# DDRmem.net
KiCad netlist of a schematic drawn in Altium Designer
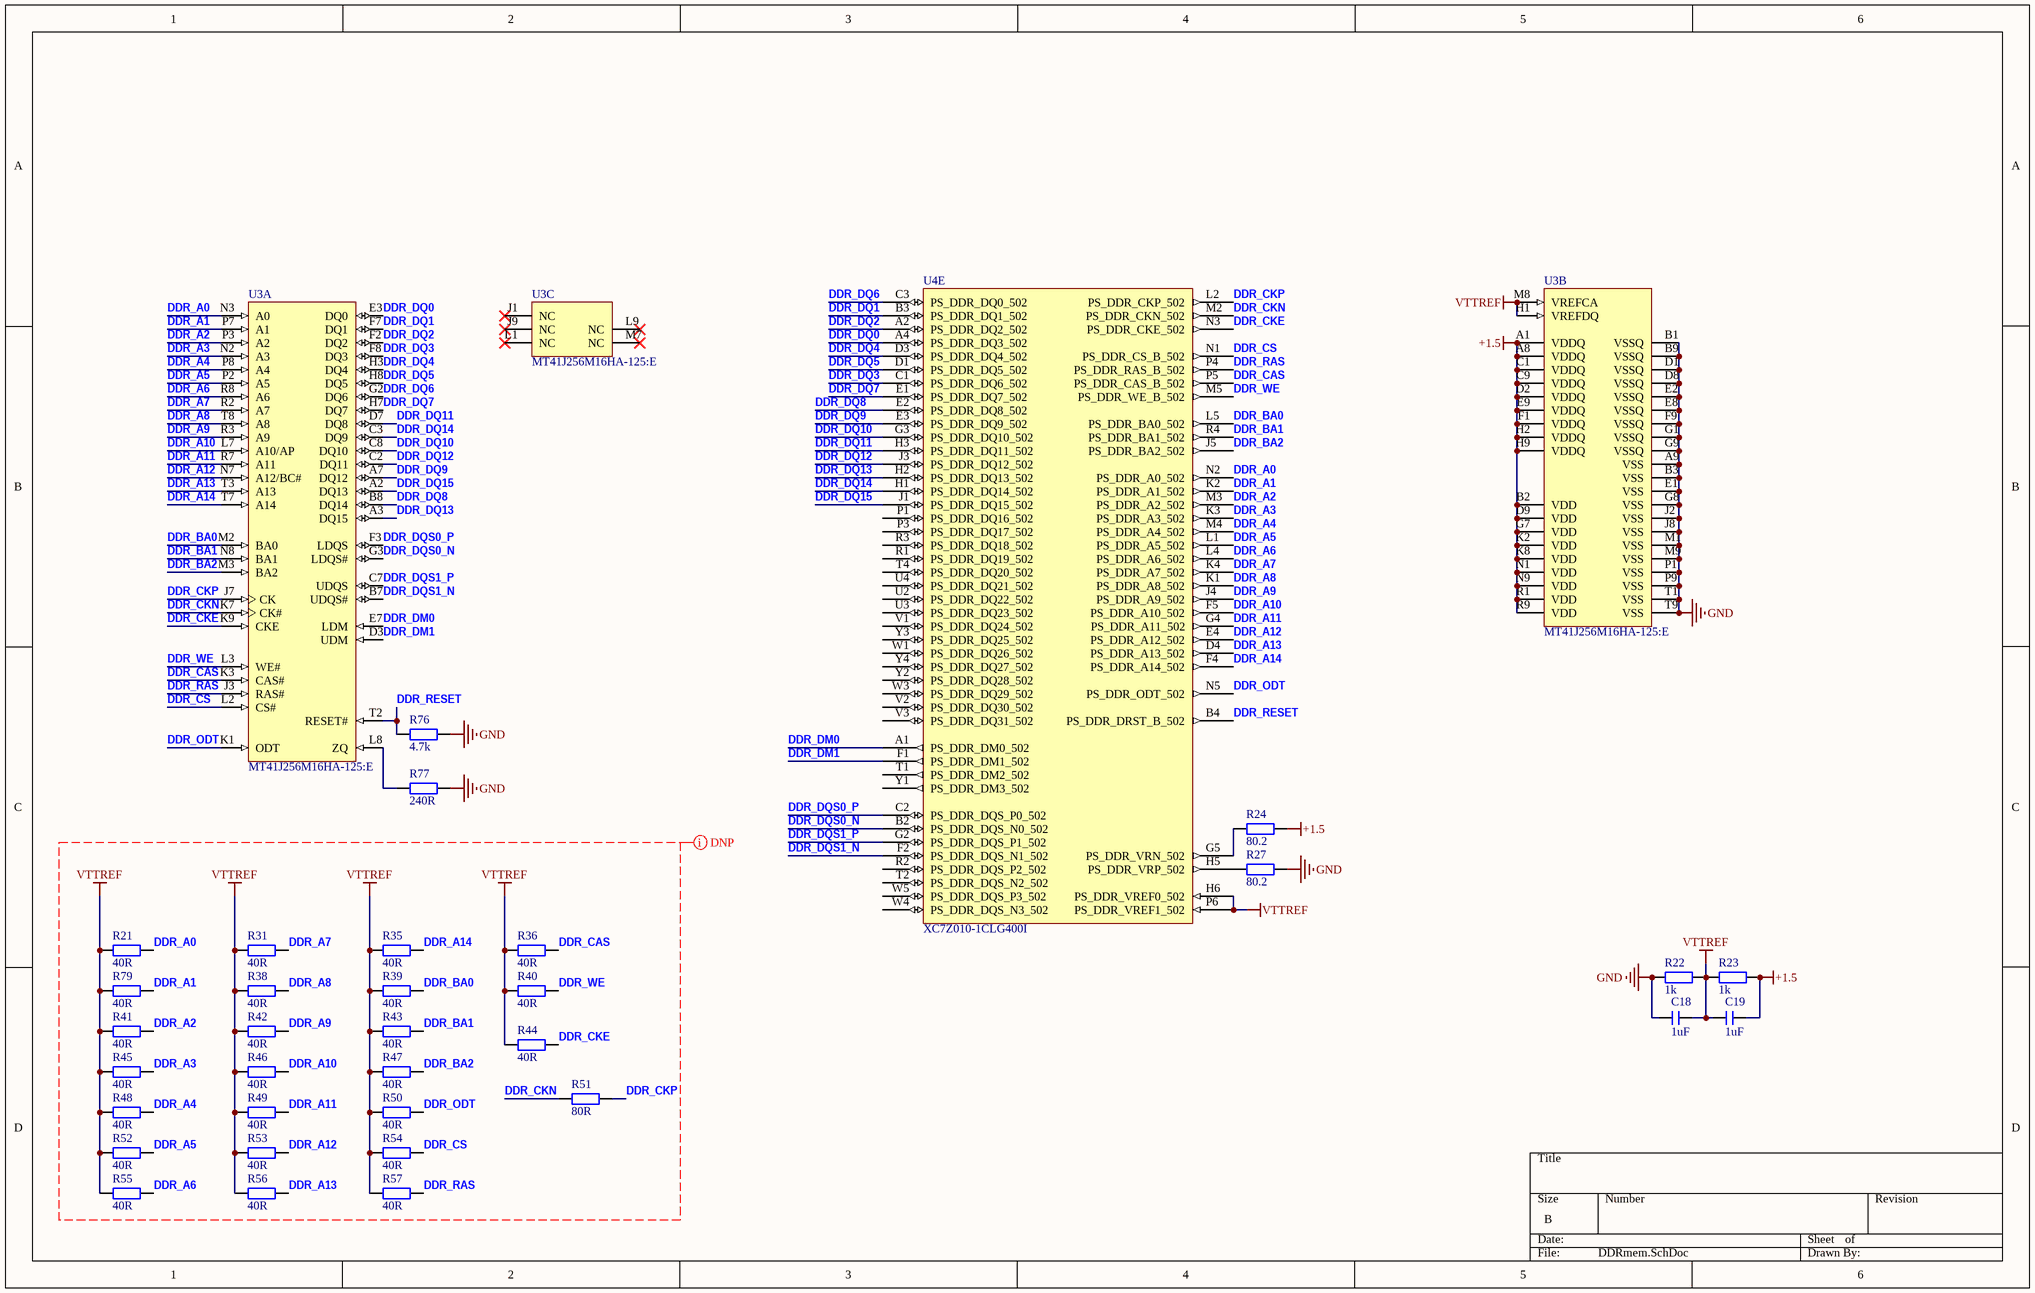
[diagram p0: DDRmem.SchDoc]

(export (version "E")
  (design (tool "Eeschema 10.0.6"))
  (components
    (comp (ref "C18")
      (value "1uF")
      (footprint "SamacSys:CAP_0201")
      (description "无极性贴片电容")
      (fields (field (name "版权归属") "源创客"))
      (libsource (lib "源创客") (part "C"))
    )
    (comp (ref "C19")
      (value "1uF")
      (footprint "SamacSys:CAP_0201")
      (description "无极性贴片电容")
      (fields (field (name "版权归属") "源创客"))
      (libsource (lib "源创客") (part "C"))
    )
    (comp (ref "R21")
      (value "40R")
      (footprint "SamacSys:RES_0201")
      (description "贴片电阻")
      (fields (field (name "版权归属") "源创客"))
      (libsource (lib "源创客") (part "R"))
    )
    (comp (ref "R22")
      (value "1k")
      (footprint "SamacSys:RES_0201")
      (description "贴片电阻")
      (fields (field (name "版权归属") "源创客"))
      (libsource (lib "源创客") (part "R"))
    )
    (comp (ref "R23")
      (value "1k")
      (footprint "SamacSys:RES_0201")
      (description "贴片电阻")
      (fields (field (name "版权归属") "源创客"))
      (libsource (lib "源创客") (part "R"))
    )
    (comp (ref "R24")
      (value "80.2")
      (footprint "SamacSys:RES_0201")
      (description "贴片电阻")
      (fields (field (name "版权归属") "源创客"))
      (libsource (lib "源创客") (part "R"))
    )
    (comp (ref "R27")
      (value "80.2")
      (footprint "SamacSys:RES_0201")
      (description "贴片电阻")
      (fields (field (name "版权归属") "源创客"))
      (libsource (lib "源创客") (part "R"))
    )
    (comp (ref "R31")
      (value "40R")
      (footprint "SamacSys:RES_0201")
      (description "贴片电阻")
      (fields (field (name "版权归属") "源创客"))
      (libsource (lib "源创客") (part "R"))
    )
    (comp (ref "R35")
      (value "40R")
      (footprint "SamacSys:RES_0201")
      (description "贴片电阻")
      (fields (field (name "版权归属") "源创客"))
      (libsource (lib "源创客") (part "R"))
    )
    (comp (ref "R36")
      (value "40R")
      (footprint "SamacSys:RES_0201")
      (description "贴片电阻")
      (fields (field (name "版权归属") "源创客"))
      (libsource (lib "源创客") (part "R"))
    )
    (comp (ref "R38")
      (value "40R")
      (footprint "SamacSys:RES_0201")
      (description "贴片电阻")
      (fields (field (name "版权归属") "源创客"))
      (libsource (lib "源创客") (part "R"))
    )
    (comp (ref "R39")
      (value "40R")
      (footprint "SamacSys:RES_0201")
      (description "贴片电阻")
      (fields (field (name "版权归属") "源创客"))
      (libsource (lib "源创客") (part "R"))
    )
    (comp (ref "R40")
      (value "40R")
      (footprint "SamacSys:RES_0201")
      (description "贴片电阻")
      (fields (field (name "版权归属") "源创客"))
      (libsource (lib "源创客") (part "R"))
    )
    (comp (ref "R41")
      (value "40R")
      (footprint "SamacSys:RES_0201")
      (description "贴片电阻")
      (fields (field (name "版权归属") "源创客"))
      (libsource (lib "源创客") (part "R"))
    )
    (comp (ref "R42")
      (value "40R")
      (footprint "SamacSys:RES_0201")
      (description "贴片电阻")
      (fields (field (name "版权归属") "源创客"))
      (libsource (lib "源创客") (part "R"))
    )
    (comp (ref "R43")
      (value "40R")
      (footprint "SamacSys:RES_0201")
      (description "贴片电阻")
      (fields (field (name "版权归属") "源创客"))
      (libsource (lib "源创客") (part "R"))
    )
    (comp (ref "R44")
      (value "40R")
      (footprint "SamacSys:RES_0201")
      (description "贴片电阻")
      (fields (field (name "版权归属") "源创客"))
      (libsource (lib "源创客") (part "R"))
    )
    (comp (ref "R45")
      (value "40R")
      (footprint "SamacSys:RES_0201")
      (description "贴片电阻")
      (fields (field (name "版权归属") "源创客"))
      (libsource (lib "源创客") (part "R"))
    )
    (comp (ref "R46")
      (value "40R")
      (footprint "SamacSys:RES_0201")
      (description "贴片电阻")
      (fields (field (name "版权归属") "源创客"))
      (libsource (lib "源创客") (part "R"))
    )
    (comp (ref "R47")
      (value "40R")
      (footprint "SamacSys:RES_0201")
      (description "贴片电阻")
      (fields (field (name "版权归属") "源创客"))
      (libsource (lib "源创客") (part "R"))
    )
    (comp (ref "R48")
      (value "40R")
      (footprint "SamacSys:RES_0201")
      (description "贴片电阻")
      (fields (field (name "版权归属") "源创客"))
      (libsource (lib "源创客") (part "R"))
    )
    (comp (ref "R49")
      (value "40R")
      (footprint "SamacSys:RES_0201")
      (description "贴片电阻")
      (fields (field (name "版权归属") "源创客"))
      (libsource (lib "源创客") (part "R"))
    )
    (comp (ref "R50")
      (value "40R")
      (footprint "SamacSys:RES_0201")
      (description "贴片电阻")
      (fields (field (name "版权归属") "源创客"))
      (libsource (lib "源创客") (part "R"))
    )
    (comp (ref "R51")
      (value "80R")
      (footprint "SamacSys:RES_0201")
      (description "贴片电阻")
      (fields (field (name "版权归属") "源创客"))
      (libsource (lib "源创客") (part "R"))
    )
    (comp (ref "R52")
      (value "40R")
      (footprint "SamacSys:RES_0201")
      (description "贴片电阻")
      (fields (field (name "版权归属") "源创客"))
      (libsource (lib "源创客") (part "R"))
    )
    (comp (ref "R53")
      (value "40R")
      (footprint "SamacSys:RES_0201")
      (description "贴片电阻")
      (fields (field (name "版权归属") "源创客"))
      (libsource (lib "源创客") (part "R"))
    )
    (comp (ref "R54")
      (value "40R")
      (footprint "SamacSys:RES_0201")
      (description "贴片电阻")
      (fields (field (name "版权归属") "源创客"))
      (libsource (lib "源创客") (part "R"))
    )
    (comp (ref "R55")
      (value "40R")
      (footprint "SamacSys:RES_0201")
      (description "贴片电阻")
      (fields (field (name "版权归属") "源创客"))
      (libsource (lib "源创客") (part "R"))
    )
    (comp (ref "R56")
      (value "40R")
      (footprint "SamacSys:RES_0201")
      (description "贴片电阻")
      (fields (field (name "版权归属") "源创客"))
      (libsource (lib "源创客") (part "R"))
    )
    (comp (ref "R57")
      (value "40R")
      (footprint "SamacSys:RES_0201")
      (description "贴片电阻")
      (fields (field (name "版权归属") "源创客"))
      (libsource (lib "源创客") (part "R"))
    )
    (comp (ref "R76")
      (value "4.7k")
      (footprint "SamacSys:RES_0402")
      (description "贴片电阻")
      (fields (field (name "版权归属") "源创客"))
      (libsource (lib "源创客") (part "R"))
    )
    (comp (ref "R77")
      (value "240R")
      (footprint "SamacSys:RES_0201")
      (description "贴片电阻")
      (fields (field (name "版权归属") "源创客"))
      (libsource (lib "源创客") (part "R"))
    )
    (comp (ref "R79")
      (value "40R")
      (footprint "SamacSys:RES_0201")
      (description "贴片电阻")
      (fields (field (name "版权归属") "源创客"))
      (libsource (lib "源创客") (part "R"))
    )
    (comp (ref "U3")
      (value "MT41J256M16HA-125:E")
      (footprint "MICT-HA-96")
      (description "4 Gb DDR3-1600 SDRAM, 256 Mb x 16, 1.25 ns, 1.5 V, 0 to 95 degC, 96-Ball FBGA, Pb-Free")
      (fields (field (name "MANUFACTURER") "Micron"))
      (libsource (lib "Altium Content Vault") (part "MICT-MT41J256M16HA-96"))
    )
    (comp (ref "U4")
      (value "XC7Z010-1CLG400I")
      (footprint "CLG400")
      (fields (field (name "GENERIC PART NUMBER") "XC7Z010"))
      (libsource (lib "Altium Content Vault") (part "XNLX-XC7Z010-CLG400"))
    )
  )
  (nets
    (net (code "1") (name "+1.5") (class "Default")
      (node (ref "C19") (pin "1") (pinfunction "1_1") (pintype "passive"))
      (node (ref "R23") (pin "1") (pinfunction "1_1") (pintype "passive"))
      (node (ref "R24") (pin "1") (pinfunction "1_1") (pintype "passive"))
      (node (ref "U3") (pin "A1") (pinfunction "VDDQ_A1") (pintype "power_in"))
      (node (ref "U3") (pin "A8") (pinfunction "VDDQ_A8") (pintype "power_in"))
      (node (ref "U3") (pin "B2") (pinfunction "VDD_B2") (pintype "power_in"))
      (node (ref "U3") (pin "C1") (pinfunction "VDDQ_C1") (pintype "power_in"))
      (node (ref "U3") (pin "C9") (pinfunction "VDDQ_C9") (pintype "power_in"))
      (node (ref "U3") (pin "D2") (pinfunction "VDDQ_D2") (pintype "power_in"))
      (node (ref "U3") (pin "D9") (pinfunction "VDD_D9") (pintype "power_in"))
      (node (ref "U3") (pin "E9") (pinfunction "VDDQ_E9") (pintype "power_in"))
      (node (ref "U3") (pin "F1") (pinfunction "VDDQ_F1") (pintype "power_in"))
      (node (ref "U3") (pin "G7") (pinfunction "VDD_G7") (pintype "power_in"))
      (node (ref "U3") (pin "H2") (pinfunction "VDDQ_H2") (pintype "power_in"))
      (node (ref "U3") (pin "H9") (pinfunction "VDDQ_H9") (pintype "power_in"))
      (node (ref "U3") (pin "K2") (pinfunction "VDD_K2") (pintype "power_in"))
      (node (ref "U3") (pin "K8") (pinfunction "VDD_K8") (pintype "power_in"))
      (node (ref "U3") (pin "N1") (pinfunction "VDD_N1") (pintype "power_in"))
      (node (ref "U3") (pin "N9") (pinfunction "VDD_N9") (pintype "power_in"))
      (node (ref "U3") (pin "R1") (pinfunction "VDD_R1") (pintype "power_in"))
      (node (ref "U3") (pin "R9") (pinfunction "VDD_R9") (pintype "power_in"))
    )
    (net (code "2") (name "/DDR_A0") (class "Default")
      (node (ref "R21") (pin "1") (pinfunction "1_1") (pintype "passive"))
      (node (ref "U3") (pin "N3") (pinfunction "A0_N3") (pintype "input"))
      (node (ref "U4") (pin "N2") (pinfunction "PS_DDR_A0_502_N2") (pintype "output"))
    )
    (net (code "3") (name "/DDR_A1") (class "Default")
      (node (ref "R79") (pin "1") (pinfunction "1_1") (pintype "passive"))
      (node (ref "U3") (pin "P7") (pinfunction "A1_P7") (pintype "input"))
      (node (ref "U4") (pin "K2") (pinfunction "PS_DDR_A1_502_K2") (pintype "output"))
    )
    (net (code "4") (name "/DDR_A2") (class "Default")
      (node (ref "R41") (pin "1") (pinfunction "1_1") (pintype "passive"))
      (node (ref "U3") (pin "P3") (pinfunction "A2_P3") (pintype "input"))
      (node (ref "U4") (pin "M3") (pinfunction "PS_DDR_A2_502_M3") (pintype "output"))
    )
    (net (code "5") (name "/DDR_A3") (class "Default")
      (node (ref "R45") (pin "1") (pinfunction "1_1") (pintype "passive"))
      (node (ref "U3") (pin "N2") (pinfunction "A3_N2") (pintype "input"))
      (node (ref "U4") (pin "K3") (pinfunction "PS_DDR_A3_502_K3") (pintype "output"))
    )
    (net (code "6") (name "/DDR_A4") (class "Default")
      (node (ref "R48") (pin "1") (pinfunction "1_1") (pintype "passive"))
      (node (ref "U3") (pin "P8") (pinfunction "A4_P8") (pintype "input"))
      (node (ref "U4") (pin "M4") (pinfunction "PS_DDR_A4_502_M4") (pintype "output"))
    )
    (net (code "7") (name "/DDR_A5") (class "Default")
      (node (ref "R52") (pin "1") (pinfunction "1_1") (pintype "passive"))
      (node (ref "U3") (pin "P2") (pinfunction "A5_P2") (pintype "input"))
      (node (ref "U4") (pin "L1") (pinfunction "PS_DDR_A5_502_L1") (pintype "output"))
    )
    (net (code "8") (name "/DDR_A6") (class "Default")
      (node (ref "R55") (pin "1") (pinfunction "1_1") (pintype "passive"))
      (node (ref "U3") (pin "R8") (pinfunction "A6_R8") (pintype "input"))
      (node (ref "U4") (pin "L4") (pinfunction "PS_DDR_A6_502_L4") (pintype "output"))
    )
    (net (code "9") (name "/DDR_A7") (class "Default")
      (node (ref "R31") (pin "1") (pinfunction "1_1") (pintype "passive"))
      (node (ref "U3") (pin "R2") (pinfunction "A7_R2") (pintype "input"))
      (node (ref "U4") (pin "K4") (pinfunction "PS_DDR_A7_502_K4") (pintype "output"))
    )
    (net (code "10") (name "/DDR_A8") (class "Default")
      (node (ref "R38") (pin "1") (pinfunction "1_1") (pintype "passive"))
      (node (ref "U3") (pin "T8") (pinfunction "A8_T8") (pintype "input"))
      (node (ref "U4") (pin "K1") (pinfunction "PS_DDR_A8_502_K1") (pintype "output"))
    )
    (net (code "11") (name "/DDR_A9") (class "Default")
      (node (ref "R42") (pin "1") (pinfunction "1_1") (pintype "passive"))
      (node (ref "U3") (pin "R3") (pinfunction "A9_R3") (pintype "input"))
      (node (ref "U4") (pin "J4") (pinfunction "PS_DDR_A9_502_J4") (pintype "output"))
    )
    (net (code "12") (name "/DDR_A10") (class "Default")
      (node (ref "R46") (pin "1") (pinfunction "1_1") (pintype "passive"))
      (node (ref "U3") (pin "L7") (pinfunction "A10/AP_L7") (pintype "input"))
      (node (ref "U4") (pin "F5") (pinfunction "PS_DDR_A10_502_F5") (pintype "output"))
    )
    (net (code "13") (name "/DDR_A11") (class "Default")
      (node (ref "R49") (pin "1") (pinfunction "1_1") (pintype "passive"))
      (node (ref "U3") (pin "R7") (pinfunction "A11_R7") (pintype "input"))
      (node (ref "U4") (pin "G4") (pinfunction "PS_DDR_A11_502_G4") (pintype "output"))
    )
    (net (code "14") (name "/DDR_A12") (class "Default")
      (node (ref "R53") (pin "1") (pinfunction "1_1") (pintype "passive"))
      (node (ref "U3") (pin "N7") (pinfunction "A12/BC#_N7") (pintype "input"))
      (node (ref "U4") (pin "E4") (pinfunction "PS_DDR_A12_502_E4") (pintype "output"))
    )
    (net (code "15") (name "/DDR_A13") (class "Default")
      (node (ref "R56") (pin "1") (pinfunction "1_1") (pintype "passive"))
      (node (ref "U3") (pin "T3") (pinfunction "A13_T3") (pintype "input"))
      (node (ref "U4") (pin "D4") (pinfunction "PS_DDR_A13_502_D4") (pintype "output"))
    )
    (net (code "16") (name "/DDR_A14") (class "Default")
      (node (ref "R35") (pin "1") (pinfunction "1_1") (pintype "passive"))
      (node (ref "U3") (pin "T7") (pinfunction "A14_T7") (pintype "input"))
      (node (ref "U4") (pin "F4") (pinfunction "PS_DDR_A14_502_F4") (pintype "output"))
    )
    (net (code "17") (name "/DDR_BA0") (class "Default")
      (node (ref "R39") (pin "1") (pinfunction "1_1") (pintype "passive"))
      (node (ref "U3") (pin "M2") (pinfunction "BA0_M2") (pintype "input"))
      (node (ref "U4") (pin "L5") (pinfunction "PS_DDR_BA0_502_L5") (pintype "output"))
    )
    (net (code "18") (name "/DDR_BA1") (class "Default")
      (node (ref "R43") (pin "1") (pinfunction "1_1") (pintype "passive"))
      (node (ref "U3") (pin "N8") (pinfunction "BA1_N8") (pintype "input"))
      (node (ref "U4") (pin "R4") (pinfunction "PS_DDR_BA1_502_R4") (pintype "output"))
    )
    (net (code "19") (name "/DDR_BA2") (class "Default")
      (node (ref "R47") (pin "1") (pinfunction "1_1") (pintype "passive"))
      (node (ref "U3") (pin "M3") (pinfunction "BA2_M3") (pintype "input"))
      (node (ref "U4") (pin "J5") (pinfunction "PS_DDR_BA2_502_J5") (pintype "output"))
    )
    (net (code "20") (name "/DDR_CAS") (class "Default")
      (node (ref "R36") (pin "1") (pinfunction "1_1") (pintype "passive"))
      (node (ref "U3") (pin "K3") (pinfunction "CAS#_K3") (pintype "input"))
      (node (ref "U4") (pin "P5") (pinfunction "PS_DDR_CAS_B_502_P5") (pintype "output"))
    )
    (net (code "21") (name "/DDR_CKE") (class "Default")
      (node (ref "R44") (pin "1") (pinfunction "1_1") (pintype "passive"))
      (node (ref "U3") (pin "K9") (pinfunction "CKE_K9") (pintype "input"))
      (node (ref "U4") (pin "N3") (pinfunction "PS_DDR_CKE_502_N3") (pintype "output"))
    )
    (net (code "22") (name "/DDR_CKN") (class "Default")
      (node (ref "R51") (pin "2") (pinfunction "2_2") (pintype "passive"))
      (node (ref "U3") (pin "K7") (pinfunction "CK#_K7") (pintype "input"))
      (node (ref "U4") (pin "M2") (pinfunction "PS_DDR_CKN_502_M2") (pintype "output"))
    )
    (net (code "23") (name "/DDR_CKP") (class "Default")
      (node (ref "R51") (pin "1") (pinfunction "1_1") (pintype "passive"))
      (node (ref "U3") (pin "J7") (pinfunction "CK_J7") (pintype "input"))
      (node (ref "U4") (pin "L2") (pinfunction "PS_DDR_CKP_502_L2") (pintype "output"))
    )
    (net (code "24") (name "/DDR_CS") (class "Default")
      (node (ref "R54") (pin "1") (pinfunction "1_1") (pintype "passive"))
      (node (ref "U3") (pin "L2") (pinfunction "CS#_L2") (pintype "input"))
      (node (ref "U4") (pin "N1") (pinfunction "PS_DDR_CS_B_502_N1") (pintype "output"))
    )
    (net (code "25") (name "/DDR_DM0") (class "Default")
      (node (ref "U3") (pin "E7") (pinfunction "LDM_E7") (pintype "input"))
      (node (ref "U4") (pin "A1") (pinfunction "PS_DDR_DM0_502_A1") (pintype "output"))
    )
    (net (code "26") (name "/DDR_DM1") (class "Default")
      (node (ref "U3") (pin "D3") (pinfunction "UDM_D3") (pintype "input"))
      (node (ref "U4") (pin "F1") (pinfunction "PS_DDR_DM1_502_F1") (pintype "output"))
    )
    (net (code "27") (name "/DDR_DQ0") (class "Default")
      (node (ref "U3") (pin "E3") (pinfunction "DQ0_E3") (pintype "bidirectional"))
      (node (ref "U4") (pin "A4") (pinfunction "PS_DDR_DQ3_502_A4") (pintype "bidirectional"))
    )
    (net (code "28") (name "/DDR_DQ1") (class "Default")
      (node (ref "U3") (pin "F7") (pinfunction "DQ1_F7") (pintype "bidirectional"))
      (node (ref "U4") (pin "B3") (pinfunction "PS_DDR_DQ1_502_B3") (pintype "bidirectional"))
    )
    (net (code "29") (name "/DDR_DQ2") (class "Default")
      (node (ref "U3") (pin "F2") (pinfunction "DQ2_F2") (pintype "bidirectional"))
      (node (ref "U4") (pin "A2") (pinfunction "PS_DDR_DQ2_502_A2") (pintype "bidirectional"))
    )
    (net (code "30") (name "/DDR_DQ3") (class "Default")
      (node (ref "U3") (pin "F8") (pinfunction "DQ3_F8") (pintype "bidirectional"))
      (node (ref "U4") (pin "C1") (pinfunction "PS_DDR_DQ6_502_C1") (pintype "bidirectional"))
    )
    (net (code "31") (name "/DDR_DQ4") (class "Default")
      (node (ref "U3") (pin "H3") (pinfunction "DQ4_H3") (pintype "bidirectional"))
      (node (ref "U4") (pin "D3") (pinfunction "PS_DDR_DQ4_502_D3") (pintype "bidirectional"))
    )
    (net (code "32") (name "/DDR_DQ5") (class "Default")
      (node (ref "U3") (pin "H8") (pinfunction "DQ5_H8") (pintype "bidirectional"))
      (node (ref "U4") (pin "D1") (pinfunction "PS_DDR_DQ5_502_D1") (pintype "bidirectional"))
    )
    (net (code "33") (name "/DDR_DQ6") (class "Default")
      (node (ref "U3") (pin "G2") (pinfunction "DQ6_G2") (pintype "bidirectional"))
      (node (ref "U4") (pin "C3") (pinfunction "PS_DDR_DQ0_502_C3") (pintype "bidirectional"))
    )
    (net (code "34") (name "/DDR_DQ7") (class "Default")
      (node (ref "U3") (pin "H7") (pinfunction "DQ7_H7") (pintype "bidirectional"))
      (node (ref "U4") (pin "E1") (pinfunction "PS_DDR_DQ7_502_E1") (pintype "bidirectional"))
    )
    (net (code "35") (name "/DDR_DQ8") (class "Default")
      (node (ref "U3") (pin "B8") (pinfunction "DQ14_B8") (pintype "bidirectional"))
      (node (ref "U4") (pin "E2") (pinfunction "PS_DDR_DQ8_502_E2") (pintype "bidirectional"))
    )
    (net (code "36") (name "/DDR_DQ9") (class "Default")
      (node (ref "U3") (pin "A7") (pinfunction "DQ12_A7") (pintype "bidirectional"))
      (node (ref "U4") (pin "E3") (pinfunction "PS_DDR_DQ9_502_E3") (pintype "bidirectional"))
    )
    (net (code "37") (name "/DDR_DQ10") (class "Default")
      (node (ref "U3") (pin "C8") (pinfunction "DQ10_C8") (pintype "bidirectional"))
      (node (ref "U4") (pin "G3") (pinfunction "PS_DDR_DQ10_502_G3") (pintype "bidirectional"))
    )
    (net (code "38") (name "/DDR_DQ11") (class "Default")
      (node (ref "U3") (pin "D7") (pinfunction "DQ8_D7") (pintype "bidirectional"))
      (node (ref "U4") (pin "H3") (pinfunction "PS_DDR_DQ11_502_H3") (pintype "bidirectional"))
    )
    (net (code "39") (name "/DDR_DQ12") (class "Default")
      (node (ref "U3") (pin "C2") (pinfunction "DQ11_C2") (pintype "bidirectional"))
      (node (ref "U4") (pin "J3") (pinfunction "PS_DDR_DQ12_502_J3") (pintype "bidirectional"))
    )
    (net (code "40") (name "/DDR_DQ13") (class "Default")
      (node (ref "U3") (pin "A3") (pinfunction "DQ15_A3") (pintype "bidirectional"))
      (node (ref "U4") (pin "H2") (pinfunction "PS_DDR_DQ13_502_H2") (pintype "bidirectional"))
    )
    (net (code "41") (name "/DDR_DQ14") (class "Default")
      (node (ref "U3") (pin "C3") (pinfunction "DQ9_C3") (pintype "bidirectional"))
      (node (ref "U4") (pin "H1") (pinfunction "PS_DDR_DQ14_502_H1") (pintype "bidirectional"))
    )
    (net (code "42") (name "/DDR_DQ15") (class "Default")
      (node (ref "U3") (pin "A2") (pinfunction "DQ13_A2") (pintype "bidirectional"))
      (node (ref "U4") (pin "J1") (pinfunction "PS_DDR_DQ15_502_J1") (pintype "bidirectional"))
    )
    (net (code "43") (name "/DDR_DQS0_N") (class "Default")
      (node (ref "U3") (pin "G3") (pinfunction "LDQS#_G3") (pintype "bidirectional"))
      (node (ref "U4") (pin "B2") (pinfunction "PS_DDR_DQS_N0_502_B2") (pintype "bidirectional"))
    )
    (net (code "44") (name "/DDR_DQS0_P") (class "Default")
      (node (ref "U3") (pin "F3") (pinfunction "LDQS_F3") (pintype "bidirectional"))
      (node (ref "U4") (pin "C2") (pinfunction "PS_DDR_DQS_P0_502_C2") (pintype "bidirectional"))
    )
    (net (code "45") (name "/DDR_DQS1_N") (class "Default")
      (node (ref "U3") (pin "B7") (pinfunction "UDQS#_B7") (pintype "bidirectional"))
      (node (ref "U4") (pin "F2") (pinfunction "PS_DDR_DQS_N1_502_F2") (pintype "bidirectional"))
    )
    (net (code "46") (name "/DDR_DQS1_P") (class "Default")
      (node (ref "U3") (pin "C7") (pinfunction "UDQS_C7") (pintype "bidirectional"))
      (node (ref "U4") (pin "G2") (pinfunction "PS_DDR_DQS_P1_502_G2") (pintype "bidirectional"))
    )
    (net (code "47") (name "/DDR_ODT") (class "Default")
      (node (ref "R50") (pin "1") (pinfunction "1_1") (pintype "passive"))
      (node (ref "U3") (pin "K1") (pinfunction "ODT_K1") (pintype "input"))
      (node (ref "U4") (pin "N5") (pinfunction "PS_DDR_ODT_502_N5") (pintype "output"))
    )
    (net (code "48") (name "/DDR_RAS") (class "Default")
      (node (ref "R57") (pin "1") (pinfunction "1_1") (pintype "passive"))
      (node (ref "U3") (pin "J3") (pinfunction "RAS#_J3") (pintype "input"))
      (node (ref "U4") (pin "P4") (pinfunction "PS_DDR_RAS_B_502_P4") (pintype "output"))
    )
    (net (code "49") (name "/DDR_RESET") (class "Default")
      (node (ref "R76") (pin "2") (pinfunction "2_2") (pintype "passive"))
      (node (ref "U3") (pin "T2") (pinfunction "RESET#_T2") (pintype "input"))
      (node (ref "U4") (pin "B4") (pinfunction "PS_DDR_DRST_B_502_B4") (pintype "output"))
    )
    (net (code "50") (name "/DDR_WE") (class "Default")
      (node (ref "R40") (pin "1") (pinfunction "1_1") (pintype "passive"))
      (node (ref "U3") (pin "L3") (pinfunction "WE#_L3") (pintype "input"))
      (node (ref "U4") (pin "M5") (pinfunction "PS_DDR_WE_B_502_M5") (pintype "output"))
    )
    (net (code "51") (name "GND") (class "Default")
      (node (ref "C18") (pin "2") (pinfunction "2_2") (pintype "passive"))
      (node (ref "R22") (pin "2") (pinfunction "2_2") (pintype "passive"))
      (node (ref "R27") (pin "1") (pinfunction "1_1") (pintype "passive"))
      (node (ref "R76") (pin "1") (pinfunction "1_1") (pintype "passive"))
      (node (ref "R77") (pin "1") (pinfunction "1_1") (pintype "passive"))
      (node (ref "U3") (pin "A9") (pinfunction "VSS_A9") (pintype "power_in"))
      (node (ref "U3") (pin "B1") (pinfunction "VSSQ_B1") (pintype "power_in"))
      (node (ref "U3") (pin "B3") (pinfunction "VSS_B3") (pintype "power_in"))
      (node (ref "U3") (pin "B9") (pinfunction "VSSQ_B9") (pintype "power_in"))
      (node (ref "U3") (pin "D1") (pinfunction "VSSQ_D1") (pintype "power_in"))
      (node (ref "U3") (pin "D8") (pinfunction "VSSQ_D8") (pintype "power_in"))
      (node (ref "U3") (pin "E1") (pinfunction "VSS_E1") (pintype "power_in"))
      (node (ref "U3") (pin "E2") (pinfunction "VSSQ_E2") (pintype "power_in"))
      (node (ref "U3") (pin "E8") (pinfunction "VSSQ_E8") (pintype "power_in"))
      (node (ref "U3") (pin "F9") (pinfunction "VSSQ_F9") (pintype "power_in"))
      (node (ref "U3") (pin "G1") (pinfunction "VSSQ_G1") (pintype "power_in"))
      (node (ref "U3") (pin "G8") (pinfunction "VSS_G8") (pintype "power_in"))
      (node (ref "U3") (pin "G9") (pinfunction "VSSQ_G9") (pintype "power_in"))
      (node (ref "U3") (pin "J2") (pinfunction "VSS_J2") (pintype "power_in"))
      (node (ref "U3") (pin "J8") (pinfunction "VSS_J8") (pintype "power_in"))
      (node (ref "U3") (pin "M1") (pinfunction "VSS_M1") (pintype "power_in"))
      (node (ref "U3") (pin "M9") (pinfunction "VSS_M9") (pintype "power_in"))
      (node (ref "U3") (pin "P1") (pinfunction "VSS_P1") (pintype "power_in"))
      (node (ref "U3") (pin "P9") (pinfunction "VSS_P9") (pintype "power_in"))
      (node (ref "U3") (pin "T1") (pinfunction "VSS_T1") (pintype "power_in"))
      (node (ref "U3") (pin "T9") (pinfunction "VSS_T9") (pintype "power_in"))
    )
    (net (code "52") (name "Net-(U3A-ZQ)") (class "Default")
      (node (ref "R77") (pin "2") (pinfunction "2_2") (pintype "passive"))
      (node (ref "U3") (pin "L8") (pinfunction "ZQ_L8") (pintype "input"))
    )
    (net (code "53") (name "Net-(U4E-PS_DDR_VRN_502)") (class "Default")
      (node (ref "R24") (pin "2") (pinfunction "2_2") (pintype "passive"))
      (node (ref "U4") (pin "G5") (pinfunction "PS_DDR_VRN_502_G5") (pintype "output"))
    )
    (net (code "54") (name "Net-(U4E-PS_DDR_VRP_502)") (class "Default")
      (node (ref "R27") (pin "2") (pinfunction "2_2") (pintype "passive"))
      (node (ref "U4") (pin "H5") (pinfunction "PS_DDR_VRP_502_H5") (pintype "output"))
    )
    (net (code "55") (name "VTTREF") (class "Default")
      (node (ref "C18") (pin "1") (pinfunction "1_1") (pintype "passive"))
      (node (ref "C19") (pin "2") (pinfunction "2_2") (pintype "passive"))
      (node (ref "R21") (pin "2") (pinfunction "2_2") (pintype "passive"))
      (node (ref "R22") (pin "1") (pinfunction "1_1") (pintype "passive"))
      (node (ref "R23") (pin "2") (pinfunction "2_2") (pintype "passive"))
      (node (ref "R31") (pin "2") (pinfunction "2_2") (pintype "passive"))
      (node (ref "R35") (pin "2") (pinfunction "2_2") (pintype "passive"))
      (node (ref "R36") (pin "2") (pinfunction "2_2") (pintype "passive"))
      (node (ref "R38") (pin "2") (pinfunction "2_2") (pintype "passive"))
      (node (ref "R39") (pin "2") (pinfunction "2_2") (pintype "passive"))
      (node (ref "R40") (pin "2") (pinfunction "2_2") (pintype "passive"))
      (node (ref "R41") (pin "2") (pinfunction "2_2") (pintype "passive"))
      (node (ref "R42") (pin "2") (pinfunction "2_2") (pintype "passive"))
      (node (ref "R43") (pin "2") (pinfunction "2_2") (pintype "passive"))
      (node (ref "R44") (pin "2") (pinfunction "2_2") (pintype "passive"))
      (node (ref "R45") (pin "2") (pinfunction "2_2") (pintype "passive"))
      (node (ref "R46") (pin "2") (pinfunction "2_2") (pintype "passive"))
      (node (ref "R47") (pin "2") (pinfunction "2_2") (pintype "passive"))
      (node (ref "R48") (pin "2") (pinfunction "2_2") (pintype "passive"))
      (node (ref "R49") (pin "2") (pinfunction "2_2") (pintype "passive"))
      (node (ref "R50") (pin "2") (pinfunction "2_2") (pintype "passive"))
      (node (ref "R52") (pin "2") (pinfunction "2_2") (pintype "passive"))
      (node (ref "R53") (pin "2") (pinfunction "2_2") (pintype "passive"))
      (node (ref "R54") (pin "2") (pinfunction "2_2") (pintype "passive"))
      (node (ref "R55") (pin "2") (pinfunction "2_2") (pintype "passive"))
      (node (ref "R56") (pin "2") (pinfunction "2_2") (pintype "passive"))
      (node (ref "R57") (pin "2") (pinfunction "2_2") (pintype "passive"))
      (node (ref "R79") (pin "2") (pinfunction "2_2") (pintype "passive"))
      (node (ref "U3") (pin "H1") (pinfunction "VREFDQ_H1") (pintype "input"))
      (node (ref "U3") (pin "M8") (pinfunction "VREFCA_M8") (pintype "input"))
      (node (ref "U4") (pin "H6") (pinfunction "PS_DDR_VREF0_502_H6") (pintype "input"))
      (node (ref "U4") (pin "P6") (pinfunction "PS_DDR_VREF1_502_P6") (pintype "input"))
    )
    (net (code "56") (name "unconnected-(U3C-NC-PadJ1)") (class "Default")
      (node (ref "U3") (pin "J1") (pinfunction "NC_J1") (pintype "passive+no_connect"))
    )
    (net (code "57") (name "unconnected-(U3C-NC-PadJ9)") (class "Default")
      (node (ref "U3") (pin "J9") (pinfunction "NC_J9") (pintype "passive+no_connect"))
    )
    (net (code "58") (name "unconnected-(U3C-NC-PadL1)") (class "Default")
      (node (ref "U3") (pin "L1") (pinfunction "NC_L1") (pintype "passive+no_connect"))
    )
    (net (code "59") (name "unconnected-(U3C-NC-PadL9)") (class "Default")
      (node (ref "U3") (pin "L9") (pinfunction "NC_L9") (pintype "passive+no_connect"))
    )
    (net (code "60") (name "unconnected-(U3C-NC-PadM7)") (class "Default")
      (node (ref "U3") (pin "M7") (pinfunction "NC_M7") (pintype "passive+no_connect"))
    )
    (net (code "61") (name "unconnected-(U4E-PS_DDR_DM2_502-PadT1)") (class "Default")
      (node (ref "U4") (pin "T1") (pinfunction "PS_DDR_DM2_502_T1") (pintype "output"))
    )
    (net (code "62") (name "unconnected-(U4E-PS_DDR_DM3_502-PadY1)") (class "Default")
      (node (ref "U4") (pin "Y1") (pinfunction "PS_DDR_DM3_502_Y1") (pintype "output"))
    )
    (net (code "63") (name "unconnected-(U4E-PS_DDR_DQ16_502-PadP1)") (class "Default")
      (node (ref "U4") (pin "P1") (pinfunction "PS_DDR_DQ16_502_P1") (pintype "bidirectional"))
    )
    (net (code "64") (name "unconnected-(U4E-PS_DDR_DQ17_502-PadP3)") (class "Default")
      (node (ref "U4") (pin "P3") (pinfunction "PS_DDR_DQ17_502_P3") (pintype "bidirectional"))
    )
    (net (code "65") (name "unconnected-(U4E-PS_DDR_DQ18_502-PadR3)") (class "Default")
      (node (ref "U4") (pin "R3") (pinfunction "PS_DDR_DQ18_502_R3") (pintype "bidirectional"))
    )
    (net (code "66") (name "unconnected-(U4E-PS_DDR_DQ19_502-PadR1)") (class "Default")
      (node (ref "U4") (pin "R1") (pinfunction "PS_DDR_DQ19_502_R1") (pintype "bidirectional"))
    )
    (net (code "67") (name "unconnected-(U4E-PS_DDR_DQ20_502-PadT4)") (class "Default")
      (node (ref "U4") (pin "T4") (pinfunction "PS_DDR_DQ20_502_T4") (pintype "bidirectional"))
    )
    (net (code "68") (name "unconnected-(U4E-PS_DDR_DQ21_502-PadU4)") (class "Default")
      (node (ref "U4") (pin "U4") (pinfunction "PS_DDR_DQ21_502_U4") (pintype "bidirectional"))
    )
    (net (code "69") (name "unconnected-(U4E-PS_DDR_DQ22_502-PadU2)") (class "Default")
      (node (ref "U4") (pin "U2") (pinfunction "PS_DDR_DQ22_502_U2") (pintype "bidirectional"))
    )
    (net (code "70") (name "unconnected-(U4E-PS_DDR_DQ23_502-PadU3)") (class "Default")
      (node (ref "U4") (pin "U3") (pinfunction "PS_DDR_DQ23_502_U3") (pintype "bidirectional"))
    )
    (net (code "71") (name "unconnected-(U4E-PS_DDR_DQ24_502-PadV1)") (class "Default")
      (node (ref "U4") (pin "V1") (pinfunction "PS_DDR_DQ24_502_V1") (pintype "bidirectional"))
    )
    (net (code "72") (name "unconnected-(U4E-PS_DDR_DQ25_502-PadY3)") (class "Default")
      (node (ref "U4") (pin "Y3") (pinfunction "PS_DDR_DQ25_502_Y3") (pintype "bidirectional"))
    )
    (net (code "73") (name "unconnected-(U4E-PS_DDR_DQ26_502-PadW1)") (class "Default")
      (node (ref "U4") (pin "W1") (pinfunction "PS_DDR_DQ26_502_W1") (pintype "bidirectional"))
    )
    (net (code "74") (name "unconnected-(U4E-PS_DDR_DQ27_502-PadY4)") (class "Default")
      (node (ref "U4") (pin "Y4") (pinfunction "PS_DDR_DQ27_502_Y4") (pintype "bidirectional"))
    )
    (net (code "75") (name "unconnected-(U4E-PS_DDR_DQ28_502-PadY2)") (class "Default")
      (node (ref "U4") (pin "Y2") (pinfunction "PS_DDR_DQ28_502_Y2") (pintype "bidirectional"))
    )
    (net (code "76") (name "unconnected-(U4E-PS_DDR_DQ29_502-PadW3)") (class "Default")
      (node (ref "U4") (pin "W3") (pinfunction "PS_DDR_DQ29_502_W3") (pintype "bidirectional"))
    )
    (net (code "77") (name "unconnected-(U4E-PS_DDR_DQ30_502-PadV2)") (class "Default")
      (node (ref "U4") (pin "V2") (pinfunction "PS_DDR_DQ30_502_V2") (pintype "bidirectional"))
    )
    (net (code "78") (name "unconnected-(U4E-PS_DDR_DQ31_502-PadV3)") (class "Default")
      (node (ref "U4") (pin "V3") (pinfunction "PS_DDR_DQ31_502_V3") (pintype "bidirectional"))
    )
    (net (code "79") (name "unconnected-(U4E-PS_DDR_DQS_N2_502-PadT2)") (class "Default")
      (node (ref "U4") (pin "T2") (pinfunction "PS_DDR_DQS_N2_502_T2") (pintype "bidirectional"))
    )
    (net (code "80") (name "unconnected-(U4E-PS_DDR_DQS_N3_502-PadW4)") (class "Default")
      (node (ref "U4") (pin "W4") (pinfunction "PS_DDR_DQS_N3_502_W4") (pintype "bidirectional"))
    )
    (net (code "81") (name "unconnected-(U4E-PS_DDR_DQS_P2_502-PadR2)") (class "Default")
      (node (ref "U4") (pin "R2") (pinfunction "PS_DDR_DQS_P2_502_R2") (pintype "bidirectional"))
    )
    (net (code "82") (name "unconnected-(U4E-PS_DDR_DQS_P3_502-PadW5)") (class "Default")
      (node (ref "U4") (pin "W5") (pinfunction "PS_DDR_DQS_P3_502_W5") (pintype "bidirectional"))
    )
  )
)
